# zmpt101b_-_3phase_din_v0_1.net
KiCad netlist of a schematic drawn in EAGLE
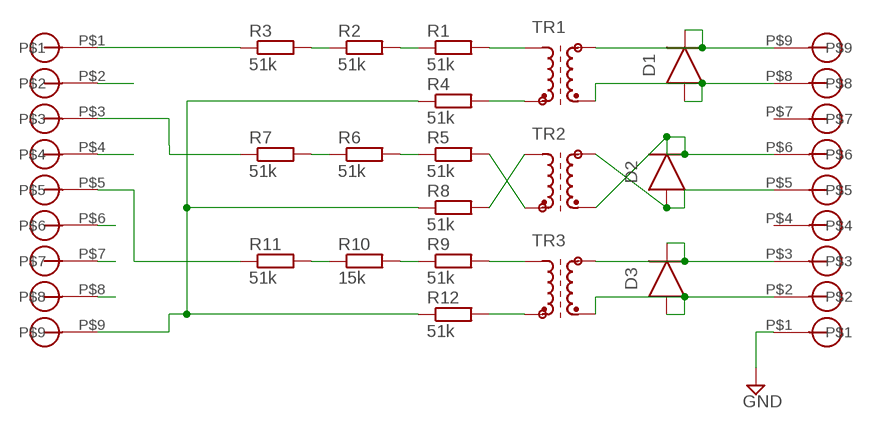
[diagram p0: schematic, sheet 1]

(export (version "E")
  (design (tool "Eeschema 10.0.6"))
  (components
    (comp (ref "D1")
      (value "DIODE_DO-219-AB(SOD123F)")
      (footprint "eagle-import:SODFL3718X115")
      (libsource (lib "eagle-import") (part "DIODEDO-219-AB(SOD123F)_"))
    )
    (comp (ref "D2")
      (value "DIODE_DO-219-AB(SOD123F)")
      (footprint "eagle-import:SODFL3718X115")
      (libsource (lib "eagle-import") (part "DIODEDO-219-AB(SOD123F)_"))
    )
    (comp (ref "D3")
      (value "DIODE_DO-219-AB(SOD123F)")
      (footprint "eagle-import:SODFL3718X115")
      (libsource (lib "eagle-import") (part "DIODEDO-219-AB(SOD123F)_"))
    )
    (comp (ref "R1")
      (value "51k")
      (footprint "eagle-import:R1206")
      (libsource (lib "eagle-import") (part "R-EU_R1206"))
    )
    (comp (ref "R2")
      (value "51k")
      (footprint "eagle-import:R1206")
      (libsource (lib "eagle-import") (part "R-EU_R1206"))
    )
    (comp (ref "R3")
      (value "51k")
      (footprint "eagle-import:R1206")
      (libsource (lib "eagle-import") (part "R-EU_R1206"))
    )
    (comp (ref "R4")
      (value "51k")
      (footprint "eagle-import:R1206")
      (libsource (lib "eagle-import") (part "R-EU_R1206"))
    )
    (comp (ref "R5")
      (value "51k")
      (footprint "eagle-import:R1206")
      (libsource (lib "eagle-import") (part "R-EU_R1206"))
    )
    (comp (ref "R6")
      (value "51k")
      (footprint "eagle-import:R1206")
      (libsource (lib "eagle-import") (part "R-EU_R1206"))
    )
    (comp (ref "R7")
      (value "51k")
      (footprint "eagle-import:R1206")
      (libsource (lib "eagle-import") (part "R-EU_R1206"))
    )
    (comp (ref "R8")
      (value "51k")
      (footprint "eagle-import:R1206")
      (libsource (lib "eagle-import") (part "R-EU_R1206"))
    )
    (comp (ref "R9")
      (value "51k")
      (footprint "eagle-import:R1206")
      (libsource (lib "eagle-import") (part "R-EU_R1206"))
    )
    (comp (ref "R10")
      (value "15k")
      (footprint "eagle-import:R1206")
      (libsource (lib "eagle-import") (part "R-EU_R1206"))
    )
    (comp (ref "R11")
      (value "51k")
      (footprint "eagle-import:R1206")
      (libsource (lib "eagle-import") (part "R-EU_R1206"))
    )
    (comp (ref "R12")
      (value "51k")
      (footprint "eagle-import:R1206")
      (libsource (lib "eagle-import") (part "R-EU_R1206"))
    )
    (comp (ref "TR1")
      (value "ZMPT101B")
      (footprint "eagle-import:ZMPT101B")
      (libsource (lib "eagle-import") (part "ZMPT101B"))
    )
    (comp (ref "TR2")
      (value "ZMPT101B")
      (footprint "eagle-import:ZMPT101B")
      (libsource (lib "eagle-import") (part "ZMPT101B"))
    )
    (comp (ref "TR3")
      (value "ZMPT101B")
      (footprint "eagle-import:ZMPT101B")
      (libsource (lib "eagle-import") (part "ZMPT101B"))
    )
    (comp (ref "U$1")
      (value "5MMBLOCK_X9")
      (footprint "eagle-import:9_5.08")
      (libsource (lib "eagle-import") (part "5MMBLOCK_X9"))
    )
    (comp (ref "U$2")
      (value "5MMBLOCK_X9")
      (footprint "eagle-import:9_5.08")
      (libsource (lib "eagle-import") (part "5MMBLOCK_X9"))
    )
  )
  (nets
    (net (code "1") (name "/P$4") (class "Default")
      (node (ref "U$2") (pin "P$4") (pinfunction "P$4_P$4") (pintype "power_in"))
    )
    (net (code "2") (name "/P$7") (class "Default")
      (node (ref "U$2") (pin "P$7") (pinfunction "P$7_P$7") (pintype "power_in"))
    )
    (net (code "3") (name "GND") (class "Default")
      (node (ref "U$2") (pin "P$1") (pinfunction "P$1_P$1") (pintype "power_in"))
    )
    (net (code "4") (name "Net-(D1-A)") (class "Default")
      (node (ref "D1") (pin "2") (pinfunction "A_2") (pintype "passive"))
      (node (ref "TR1") (pin "P$2") (pinfunction "E2_P$2") (pintype "passive"))
      (node (ref "U$2") (pin "P$8") (pinfunction "P$8_P$8") (pintype "power_in"))
    )
    (net (code "5") (name "Net-(D1-C)") (class "Default")
      (node (ref "D1") (pin "1") (pinfunction "C_1") (pintype "passive"))
      (node (ref "TR1") (pin "P$1") (pinfunction "A2_P$1") (pintype "passive"))
      (node (ref "U$2") (pin "P$9") (pinfunction "P$9_P$9") (pintype "power_in"))
    )
    (net (code "6") (name "Net-(D2-A)") (class "Default")
      (node (ref "D2") (pin "2") (pinfunction "A_2") (pintype "passive"))
      (node (ref "TR2") (pin "P$1") (pinfunction "A2_P$1") (pintype "passive"))
      (node (ref "U$2") (pin "P$5") (pinfunction "P$5_P$5") (pintype "power_in"))
    )
    (net (code "7") (name "Net-(D2-C)") (class "Default")
      (node (ref "D2") (pin "1") (pinfunction "C_1") (pintype "passive"))
      (node (ref "TR2") (pin "P$2") (pinfunction "E2_P$2") (pintype "passive"))
      (node (ref "U$2") (pin "P$6") (pinfunction "P$6_P$6") (pintype "power_in"))
    )
    (net (code "8") (name "Net-(D3-A)") (class "Default")
      (node (ref "D3") (pin "2") (pinfunction "A_2") (pintype "passive"))
      (node (ref "TR3") (pin "P$2") (pinfunction "E2_P$2") (pintype "passive"))
      (node (ref "U$2") (pin "P$2") (pinfunction "P$2_P$2") (pintype "power_in"))
    )
    (net (code "9") (name "Net-(D3-C)") (class "Default")
      (node (ref "D3") (pin "1") (pinfunction "C_1") (pintype "passive"))
      (node (ref "TR3") (pin "P$1") (pinfunction "A2_P$1") (pintype "passive"))
      (node (ref "U$2") (pin "P$3") (pinfunction "P$3_P$3") (pintype "power_in"))
    )
    (net (code "10") (name "Net-(R1-Pad1)") (class "Default")
      (node (ref "R1") (pin "1") (pinfunction "1_1") (pintype "passive"))
      (node (ref "R2") (pin "2") (pinfunction "2_2") (pintype "passive"))
    )
    (net (code "11") (name "Net-(R2-Pad1)") (class "Default")
      (node (ref "R2") (pin "1") (pinfunction "1_1") (pintype "passive"))
      (node (ref "R3") (pin "2") (pinfunction "2_2") (pintype "passive"))
    )
    (net (code "12") (name "Net-(R3-Pad1)") (class "Default")
      (node (ref "R3") (pin "1") (pinfunction "1_1") (pintype "passive"))
      (node (ref "U$1") (pin "P$1") (pinfunction "P$1_P$1") (pintype "power_in"))
    )
    (net (code "13") (name "Net-(R5-Pad1)") (class "Default")
      (node (ref "R5") (pin "1") (pinfunction "1_1") (pintype "passive"))
      (node (ref "R6") (pin "2") (pinfunction "2_2") (pintype "passive"))
    )
    (net (code "14") (name "Net-(R6-Pad1)") (class "Default")
      (node (ref "R6") (pin "1") (pinfunction "1_1") (pintype "passive"))
      (node (ref "R7") (pin "2") (pinfunction "2_2") (pintype "passive"))
    )
    (net (code "15") (name "Net-(R7-Pad1)") (class "Default")
      (node (ref "R7") (pin "1") (pinfunction "1_1") (pintype "passive"))
      (node (ref "U$1") (pin "P$3") (pinfunction "P$3_P$3") (pintype "power_in"))
    )
    (net (code "16") (name "Net-(R10-Pad1)") (class "Default")
      (node (ref "R10") (pin "1") (pinfunction "1_1") (pintype "passive"))
      (node (ref "R11") (pin "2") (pinfunction "2_2") (pintype "passive"))
    )
    (net (code "17") (name "Net-(R10-Pad2)") (class "Default")
      (node (ref "R10") (pin "2") (pinfunction "2_2") (pintype "passive"))
      (node (ref "R9") (pin "1") (pinfunction "1_1") (pintype "passive"))
    )
    (net (code "18") (name "Net-(R11-Pad1)") (class "Default")
      (node (ref "R11") (pin "1") (pinfunction "1_1") (pintype "passive"))
      (node (ref "U$1") (pin "P$5") (pinfunction "P$5_P$5") (pintype "power_in"))
    )
    (net (code "19") (name "Net-(R12-Pad1)") (class "Default")
      (node (ref "R12") (pin "1") (pinfunction "1_1") (pintype "passive"))
      (node (ref "R4") (pin "1") (pinfunction "1_1") (pintype "passive"))
      (node (ref "R8") (pin "1") (pinfunction "1_1") (pintype "passive"))
      (node (ref "U$1") (pin "P$9") (pinfunction "P$9_P$9") (pintype "power_in"))
    )
    (net (code "20") (name "Net-(TR1-A1)") (class "Default")
      (node (ref "R1") (pin "2") (pinfunction "2_2") (pintype "passive"))
      (node (ref "TR1") (pin "P$4") (pinfunction "A1_P$4") (pintype "passive"))
    )
    (net (code "21") (name "Net-(TR1-E1)") (class "Default")
      (node (ref "R4") (pin "2") (pinfunction "2_2") (pintype "passive"))
      (node (ref "TR1") (pin "P$3") (pinfunction "E1_P$3") (pintype "passive"))
    )
    (net (code "22") (name "Net-(TR2-A1)") (class "Default")
      (node (ref "R8") (pin "2") (pinfunction "2_2") (pintype "passive"))
      (node (ref "TR2") (pin "P$4") (pinfunction "A1_P$4") (pintype "passive"))
    )
    (net (code "23") (name "Net-(TR2-E1)") (class "Default")
      (node (ref "R5") (pin "2") (pinfunction "2_2") (pintype "passive"))
      (node (ref "TR2") (pin "P$3") (pinfunction "E1_P$3") (pintype "passive"))
    )
    (net (code "24") (name "Net-(TR3-A1)") (class "Default")
      (node (ref "R9") (pin "2") (pinfunction "2_2") (pintype "passive"))
      (node (ref "TR3") (pin "P$4") (pinfunction "A1_P$4") (pintype "passive"))
    )
    (net (code "25") (name "Net-(TR3-E1)") (class "Default")
      (node (ref "R12") (pin "2") (pinfunction "2_2") (pintype "passive"))
      (node (ref "TR3") (pin "P$3") (pinfunction "E1_P$3") (pintype "passive"))
    )
    (net (code "26") (name "unconnected-(U$1-PadP$2)") (class "Default")
      (node (ref "U$1") (pin "P$2") (pinfunction "P$2_P$2") (pintype "power_in"))
    )
    (net (code "27") (name "unconnected-(U$1-PadP$4)") (class "Default")
      (node (ref "U$1") (pin "P$4") (pinfunction "P$4_P$4") (pintype "power_in"))
    )
    (net (code "28") (name "unconnected-(U$1-PadP$6)") (class "Default")
      (node (ref "U$1") (pin "P$6") (pinfunction "P$6_P$6") (pintype "power_in"))
    )
    (net (code "29") (name "unconnected-(U$1-PadP$7)") (class "Default")
      (node (ref "U$1") (pin "P$7") (pinfunction "P$7_P$7") (pintype "power_in"))
    )
    (net (code "30") (name "unconnected-(U$1-PadP$8)") (class "Default")
      (node (ref "U$1") (pin "P$8") (pinfunction "P$8_P$8") (pintype "power_in"))
    )
  )
)
